# FuseCircuit.net
KiCad netlist of a schematic drawn in Altium Designer
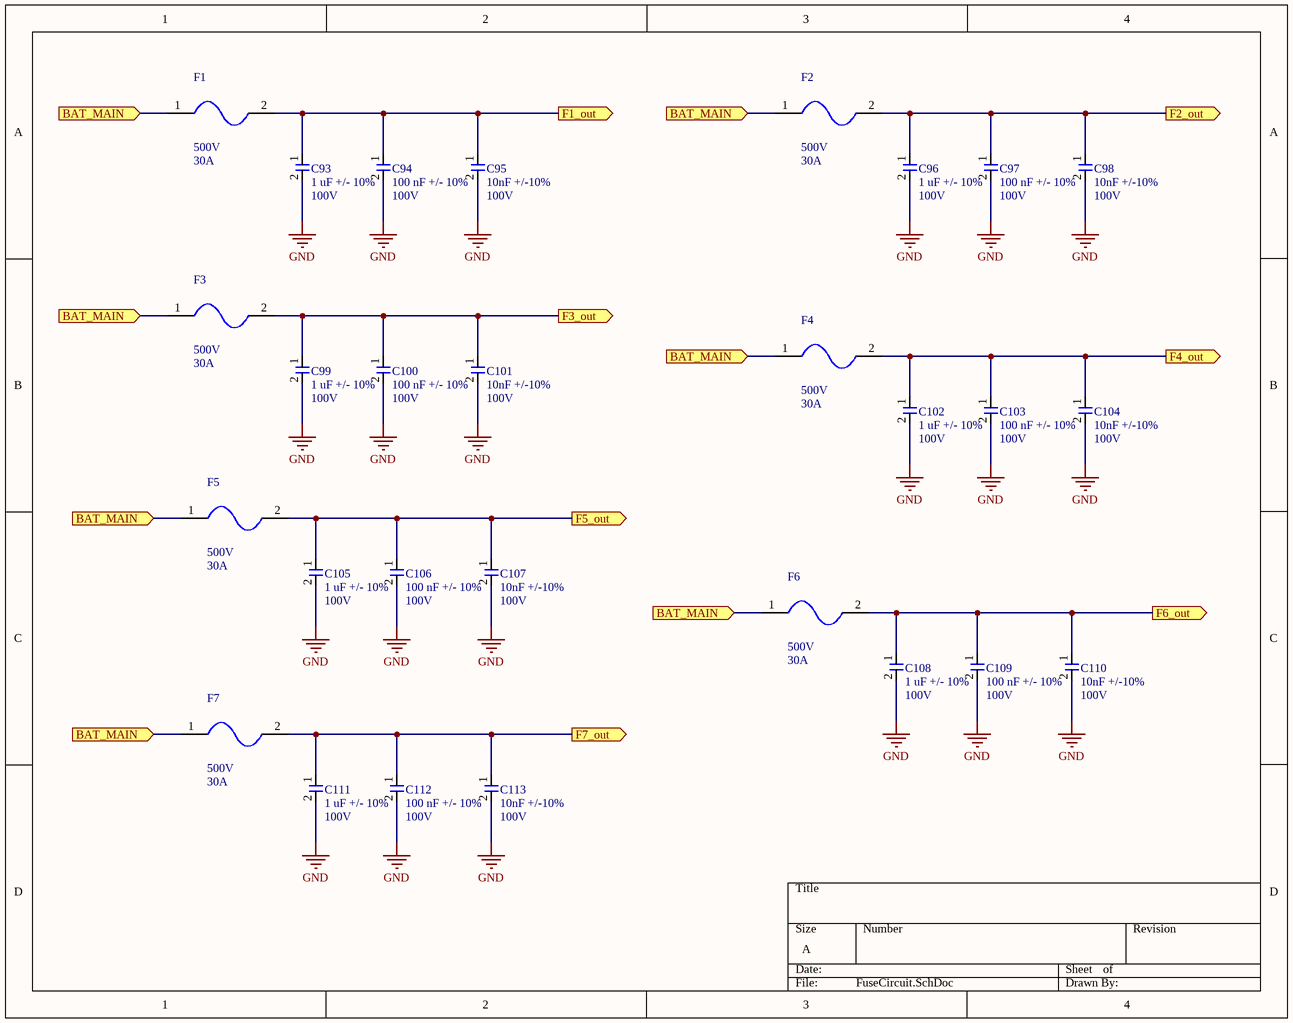
[diagram p0: FuseCircuit.SchDoc]

(export (version "E")
  (design (tool "Eeschema 10.0.6"))
  (components
    (comp (ref "C93")
      (value "C1206X105K101T")
      (footprint "CAP-1206 - duplicate")
      (description "100V 1uF X7R ±10% 1206 Multilayer Ceramic Capacitors MLCC - SMD/SMT ROHS")
      (fields
        (field (name "JLC PART NUMBER") "C106026")
        (field (name "CAPACITANCE") "1 uF +/- 10%")
        (field (name "VOLTAGE") "100V")
      )
      (libsource (lib "MasterLib") (part "CAP-1U-0004-JLC"))
    )
    (comp (ref "C94")
      (value "CC0603KRX7R0BB104")
      (footprint "CAP-0603")
      (description "100V 100nF X7R ±10% 0603 Multilayer Ceramic Capacitors MLCC - SMD/SMT ROHS")
      (fields
        (field (name "JLC PART NUMBER") "C113803")
        (field (name "CAPACITANCE") "100 nF +/- 10%")
        (field (name "VOLTAGE") "100V")
      )
      (libsource (lib "MasterLib") (part "CAP-100N-0002-JLC"))
    )
    (comp (ref "C95")
      (value "CC0603KRX7R0BB103")
      (footprint "CAP-0603")
      (description "100V 10nF X7R ±10% 0603 Multilayer Ceramic Capacitors MLCC - SMD/SMT ROHS")
      (fields
        (field (name "MANUFACTURER") "Yageo")
        (field (name "JLC PART NUMBER") "C107059")
        (field (name "CAPACITANCE") "10nF +/-10%")
        (field (name "VOLTAGE RATING") "100V")
      )
      (libsource (lib "MasterLib") (part "CAP-10N-0003-JLC"))
    )
    (comp (ref "C96")
      (value "C1206X105K101T")
      (footprint "CAP-1206 - duplicate")
      (description "100V 1uF X7R ±10% 1206 Multilayer Ceramic Capacitors MLCC - SMD/SMT ROHS")
      (fields
        (field (name "JLC PART NUMBER") "C106026")
        (field (name "CAPACITANCE") "1 uF +/- 10%")
        (field (name "VOLTAGE") "100V")
      )
      (libsource (lib "MasterLib") (part "CAP-1U-0004-JLC"))
    )
    (comp (ref "C97")
      (value "CC0603KRX7R0BB104")
      (footprint "CAP-0603")
      (description "100V 100nF X7R ±10% 0603 Multilayer Ceramic Capacitors MLCC - SMD/SMT ROHS")
      (fields
        (field (name "JLC PART NUMBER") "C113803")
        (field (name "CAPACITANCE") "100 nF +/- 10%")
        (field (name "VOLTAGE") "100V")
      )
      (libsource (lib "MasterLib") (part "CAP-100N-0002-JLC"))
    )
    (comp (ref "C98")
      (value "CC0603KRX7R0BB103")
      (footprint "CAP-0603")
      (description "100V 10nF X7R ±10% 0603 Multilayer Ceramic Capacitors MLCC - SMD/SMT ROHS")
      (fields
        (field (name "MANUFACTURER") "Yageo")
        (field (name "JLC PART NUMBER") "C107059")
        (field (name "CAPACITANCE") "10nF +/-10%")
        (field (name "VOLTAGE RATING") "100V")
      )
      (libsource (lib "MasterLib") (part "CAP-10N-0003-JLC"))
    )
    (comp (ref "C99")
      (value "C1206X105K101T")
      (footprint "CAP-1206 - duplicate")
      (description "100V 1uF X7R ±10% 1206 Multilayer Ceramic Capacitors MLCC - SMD/SMT ROHS")
      (fields
        (field (name "JLC PART NUMBER") "C106026")
        (field (name "CAPACITANCE") "1 uF +/- 10%")
        (field (name "VOLTAGE") "100V")
      )
      (libsource (lib "MasterLib") (part "CAP-1U-0004-JLC"))
    )
    (comp (ref "C100")
      (value "CC0603KRX7R0BB104")
      (footprint "CAP-0603")
      (description "100V 100nF X7R ±10% 0603 Multilayer Ceramic Capacitors MLCC - SMD/SMT ROHS")
      (fields
        (field (name "JLC PART NUMBER") "C113803")
        (field (name "CAPACITANCE") "100 nF +/- 10%")
        (field (name "VOLTAGE") "100V")
      )
      (libsource (lib "MasterLib") (part "CAP-100N-0002-JLC"))
    )
    (comp (ref "C101")
      (value "CC0603KRX7R0BB103")
      (footprint "CAP-0603")
      (description "100V 10nF X7R ±10% 0603 Multilayer Ceramic Capacitors MLCC - SMD/SMT ROHS")
      (fields
        (field (name "MANUFACTURER") "Yageo")
        (field (name "JLC PART NUMBER") "C107059")
        (field (name "CAPACITANCE") "10nF +/-10%")
        (field (name "VOLTAGE RATING") "100V")
      )
      (libsource (lib "MasterLib") (part "CAP-10N-0003-JLC"))
    )
    (comp (ref "C102")
      (value "C1206X105K101T")
      (footprint "CAP-1206 - duplicate")
      (description "100V 1uF X7R ±10% 1206 Multilayer Ceramic Capacitors MLCC - SMD/SMT ROHS")
      (fields
        (field (name "JLC PART NUMBER") "C106026")
        (field (name "CAPACITANCE") "1 uF +/- 10%")
        (field (name "VOLTAGE") "100V")
      )
      (libsource (lib "MasterLib") (part "CAP-1U-0004-JLC"))
    )
    (comp (ref "C103")
      (value "CC0603KRX7R0BB104")
      (footprint "CAP-0603")
      (description "100V 100nF X7R ±10% 0603 Multilayer Ceramic Capacitors MLCC - SMD/SMT ROHS")
      (fields
        (field (name "JLC PART NUMBER") "C113803")
        (field (name "CAPACITANCE") "100 nF +/- 10%")
        (field (name "VOLTAGE") "100V")
      )
      (libsource (lib "MasterLib") (part "CAP-100N-0002-JLC"))
    )
    (comp (ref "C104")
      (value "CC0603KRX7R0BB103")
      (footprint "CAP-0603")
      (description "100V 10nF X7R ±10% 0603 Multilayer Ceramic Capacitors MLCC - SMD/SMT ROHS")
      (fields
        (field (name "MANUFACTURER") "Yageo")
        (field (name "JLC PART NUMBER") "C107059")
        (field (name "CAPACITANCE") "10nF +/-10%")
        (field (name "VOLTAGE RATING") "100V")
      )
      (libsource (lib "MasterLib") (part "CAP-10N-0003-JLC"))
    )
    (comp (ref "C105")
      (value "C1206X105K101T")
      (footprint "CAP-1206 - duplicate")
      (description "100V 1uF X7R ±10% 1206 Multilayer Ceramic Capacitors MLCC - SMD/SMT ROHS")
      (fields
        (field (name "JLC PART NUMBER") "C106026")
        (field (name "CAPACITANCE") "1 uF +/- 10%")
        (field (name "VOLTAGE") "100V")
      )
      (libsource (lib "MasterLib") (part "CAP-1U-0004-JLC"))
    )
    (comp (ref "C106")
      (value "CC0603KRX7R0BB104")
      (footprint "CAP-0603")
      (description "100V 100nF X7R ±10% 0603 Multilayer Ceramic Capacitors MLCC - SMD/SMT ROHS")
      (fields
        (field (name "JLC PART NUMBER") "C113803")
        (field (name "CAPACITANCE") "100 nF +/- 10%")
        (field (name "VOLTAGE") "100V")
      )
      (libsource (lib "MasterLib") (part "CAP-100N-0002-JLC"))
    )
    (comp (ref "C107")
      (value "CC0603KRX7R0BB103")
      (footprint "CAP-0603")
      (description "100V 10nF X7R ±10% 0603 Multilayer Ceramic Capacitors MLCC - SMD/SMT ROHS")
      (fields
        (field (name "MANUFACTURER") "Yageo")
        (field (name "JLC PART NUMBER") "C107059")
        (field (name "CAPACITANCE") "10nF +/-10%")
        (field (name "VOLTAGE RATING") "100V")
      )
      (libsource (lib "MasterLib") (part "CAP-10N-0003-JLC"))
    )
    (comp (ref "C108")
      (value "C1206X105K101T")
      (footprint "CAP-1206 - duplicate")
      (description "100V 1uF X7R ±10% 1206 Multilayer Ceramic Capacitors MLCC - SMD/SMT ROHS")
      (fields
        (field (name "JLC PART NUMBER") "C106026")
        (field (name "CAPACITANCE") "1 uF +/- 10%")
        (field (name "VOLTAGE") "100V")
      )
      (libsource (lib "MasterLib") (part "CAP-1U-0004-JLC"))
    )
    (comp (ref "C109")
      (value "CC0603KRX7R0BB104")
      (footprint "CAP-0603")
      (description "100V 100nF X7R ±10% 0603 Multilayer Ceramic Capacitors MLCC - SMD/SMT ROHS")
      (fields
        (field (name "JLC PART NUMBER") "C113803")
        (field (name "CAPACITANCE") "100 nF +/- 10%")
        (field (name "VOLTAGE") "100V")
      )
      (libsource (lib "MasterLib") (part "CAP-100N-0002-JLC"))
    )
    (comp (ref "C110")
      (value "CC0603KRX7R0BB103")
      (footprint "CAP-0603")
      (description "100V 10nF X7R ±10% 0603 Multilayer Ceramic Capacitors MLCC - SMD/SMT ROHS")
      (fields
        (field (name "MANUFACTURER") "Yageo")
        (field (name "JLC PART NUMBER") "C107059")
        (field (name "CAPACITANCE") "10nF +/-10%")
        (field (name "VOLTAGE RATING") "100V")
      )
      (libsource (lib "MasterLib") (part "CAP-10N-0003-JLC"))
    )
    (comp (ref "C111")
      (value "C1206X105K101T")
      (footprint "CAP-1206 - duplicate")
      (description "100V 1uF X7R ±10% 1206 Multilayer Ceramic Capacitors MLCC - SMD/SMT ROHS")
      (fields
        (field (name "JLC PART NUMBER") "C106026")
        (field (name "CAPACITANCE") "1 uF +/- 10%")
        (field (name "VOLTAGE") "100V")
      )
      (libsource (lib "MasterLib") (part "CAP-1U-0004-JLC"))
    )
    (comp (ref "C112")
      (value "CC0603KRX7R0BB104")
      (footprint "CAP-0603")
      (description "100V 100nF X7R ±10% 0603 Multilayer Ceramic Capacitors MLCC - SMD/SMT ROHS")
      (fields
        (field (name "JLC PART NUMBER") "C113803")
        (field (name "CAPACITANCE") "100 nF +/- 10%")
        (field (name "VOLTAGE") "100V")
      )
      (libsource (lib "MasterLib") (part "CAP-100N-0002-JLC"))
    )
    (comp (ref "C113")
      (value "CC0603KRX7R0BB103")
      (footprint "CAP-0603")
      (description "100V 10nF X7R ±10% 0603 Multilayer Ceramic Capacitors MLCC - SMD/SMT ROHS")
      (fields
        (field (name "MANUFACTURER") "Yageo")
        (field (name "JLC PART NUMBER") "C107059")
        (field (name "CAPACITANCE") "10nF +/-10%")
        (field (name "VOLTAGE RATING") "100V")
      )
      (libsource (lib "MasterLib") (part "CAP-10N-0003-JLC"))
    )
    (comp (ref "F1")
      (value "3568")
      (footprint "FUSE-ATM-0001")
      (description "Fuse Holder 30 A 500V 1 Circuit Blade Through Hole")
      (fields (field (name "VOLTAGE RATING") "500V") (field (name "CURRENT") "30A"))
      (libsource (lib "MasterLib") (part "FUSE-ATM-0001"))
    )
    (comp (ref "F2")
      (value "3568")
      (footprint "FUSE-ATM-0001")
      (description "Fuse Holder 30 A 500V 1 Circuit Blade Through Hole")
      (fields (field (name "VOLTAGE RATING") "500V") (field (name "CURRENT") "30A"))
      (libsource (lib "MasterLib") (part "FUSE-ATM-0001"))
    )
    (comp (ref "F3")
      (value "3568")
      (footprint "FUSE-ATM-0001")
      (description "Fuse Holder 30 A 500V 1 Circuit Blade Through Hole")
      (fields (field (name "VOLTAGE RATING") "500V") (field (name "CURRENT") "30A"))
      (libsource (lib "MasterLib") (part "FUSE-ATM-0001"))
    )
    (comp (ref "F4")
      (value "3568")
      (footprint "FUSE-ATM-0001")
      (description "Fuse Holder 30 A 500V 1 Circuit Blade Through Hole")
      (fields (field (name "VOLTAGE RATING") "500V") (field (name "CURRENT") "30A"))
      (libsource (lib "MasterLib") (part "FUSE-ATM-0001"))
    )
    (comp (ref "F5")
      (value "3568")
      (footprint "FUSE-ATM-0001")
      (description "Fuse Holder 30 A 500V 1 Circuit Blade Through Hole")
      (fields (field (name "VOLTAGE RATING") "500V") (field (name "CURRENT") "30A"))
      (libsource (lib "MasterLib") (part "FUSE-ATM-0001"))
    )
    (comp (ref "F6")
      (value "3568")
      (footprint "FUSE-ATM-0001")
      (description "Fuse Holder 30 A 500V 1 Circuit Blade Through Hole")
      (fields (field (name "VOLTAGE RATING") "500V") (field (name "CURRENT") "30A"))
      (libsource (lib "MasterLib") (part "FUSE-ATM-0001"))
    )
    (comp (ref "F7")
      (value "3568")
      (footprint "FUSE-ATM-0001")
      (description "Fuse Holder 30 A 500V 1 Circuit Blade Through Hole")
      (fields (field (name "VOLTAGE RATING") "500V") (field (name "CURRENT") "30A"))
      (libsource (lib "MasterLib") (part "FUSE-ATM-0001"))
    )
  )
  (nets
    (net (code "1") (name "/BAT_MAIN") (class "Default")
      (node (ref "F1") (pin "1") (pinfunction "0_1") (pintype "passive"))
      (node (ref "F2") (pin "1") (pinfunction "0_1") (pintype "passive"))
      (node (ref "F3") (pin "1") (pinfunction "0_1") (pintype "passive"))
      (node (ref "F4") (pin "1") (pinfunction "0_1") (pintype "passive"))
      (node (ref "F5") (pin "1") (pinfunction "0_1") (pintype "passive"))
      (node (ref "F6") (pin "1") (pinfunction "0_1") (pintype "passive"))
      (node (ref "F7") (pin "1") (pinfunction "0_1") (pintype "passive"))
    )
    (net (code "2") (name "/F1_out") (class "Default")
      (node (ref "C93") (pin "1") (pinfunction "1_1") (pintype "passive"))
      (node (ref "C94") (pin "1") (pinfunction "1_1") (pintype "passive"))
      (node (ref "C95") (pin "1") (pinfunction "1_1") (pintype "passive"))
      (node (ref "F1") (pin "2") (pinfunction "1_2") (pintype "passive"))
    )
    (net (code "3") (name "/F2_out") (class "Default")
      (node (ref "C96") (pin "1") (pinfunction "1_1") (pintype "passive"))
      (node (ref "C97") (pin "1") (pinfunction "1_1") (pintype "passive"))
      (node (ref "C98") (pin "1") (pinfunction "1_1") (pintype "passive"))
      (node (ref "F2") (pin "2") (pinfunction "1_2") (pintype "passive"))
    )
    (net (code "4") (name "/F3_out") (class "Default")
      (node (ref "C100") (pin "1") (pinfunction "1_1") (pintype "passive"))
      (node (ref "C101") (pin "1") (pinfunction "1_1") (pintype "passive"))
      (node (ref "C99") (pin "1") (pinfunction "1_1") (pintype "passive"))
      (node (ref "F3") (pin "2") (pinfunction "1_2") (pintype "passive"))
    )
    (net (code "5") (name "/F4_out") (class "Default")
      (node (ref "C102") (pin "1") (pinfunction "1_1") (pintype "passive"))
      (node (ref "C103") (pin "1") (pinfunction "1_1") (pintype "passive"))
      (node (ref "C104") (pin "1") (pinfunction "1_1") (pintype "passive"))
      (node (ref "F4") (pin "2") (pinfunction "1_2") (pintype "passive"))
    )
    (net (code "6") (name "/F5_out") (class "Default")
      (node (ref "C105") (pin "1") (pinfunction "1_1") (pintype "passive"))
      (node (ref "C106") (pin "1") (pinfunction "1_1") (pintype "passive"))
      (node (ref "C107") (pin "1") (pinfunction "1_1") (pintype "passive"))
      (node (ref "F5") (pin "2") (pinfunction "1_2") (pintype "passive"))
    )
    (net (code "7") (name "/F6_out") (class "Default")
      (node (ref "C108") (pin "1") (pinfunction "1_1") (pintype "passive"))
      (node (ref "C109") (pin "1") (pinfunction "1_1") (pintype "passive"))
      (node (ref "C110") (pin "1") (pinfunction "1_1") (pintype "passive"))
      (node (ref "F6") (pin "2") (pinfunction "1_2") (pintype "passive"))
    )
    (net (code "8") (name "/F7_out") (class "Default")
      (node (ref "C111") (pin "1") (pinfunction "1_1") (pintype "passive"))
      (node (ref "C112") (pin "1") (pinfunction "1_1") (pintype "passive"))
      (node (ref "C113") (pin "1") (pinfunction "1_1") (pintype "passive"))
      (node (ref "F7") (pin "2") (pinfunction "1_2") (pintype "passive"))
    )
    (net (code "9") (name "GND") (class "Default")
      (node (ref "C100") (pin "2") (pinfunction "2_2") (pintype "passive"))
      (node (ref "C101") (pin "2") (pinfunction "2_2") (pintype "passive"))
      (node (ref "C102") (pin "2") (pinfunction "2_2") (pintype "passive"))
      (node (ref "C103") (pin "2") (pinfunction "2_2") (pintype "passive"))
      (node (ref "C104") (pin "2") (pinfunction "2_2") (pintype "passive"))
      (node (ref "C105") (pin "2") (pinfunction "2_2") (pintype "passive"))
      (node (ref "C106") (pin "2") (pinfunction "2_2") (pintype "passive"))
      (node (ref "C107") (pin "2") (pinfunction "2_2") (pintype "passive"))
      (node (ref "C108") (pin "2") (pinfunction "2_2") (pintype "passive"))
      (node (ref "C109") (pin "2") (pinfunction "2_2") (pintype "passive"))
      (node (ref "C110") (pin "2") (pinfunction "2_2") (pintype "passive"))
      (node (ref "C111") (pin "2") (pinfunction "2_2") (pintype "passive"))
      (node (ref "C112") (pin "2") (pinfunction "2_2") (pintype "passive"))
      (node (ref "C113") (pin "2") (pinfunction "2_2") (pintype "passive"))
      (node (ref "C93") (pin "2") (pinfunction "2_2") (pintype "passive"))
      (node (ref "C94") (pin "2") (pinfunction "2_2") (pintype "passive"))
      (node (ref "C95") (pin "2") (pinfunction "2_2") (pintype "passive"))
      (node (ref "C96") (pin "2") (pinfunction "2_2") (pintype "passive"))
      (node (ref "C97") (pin "2") (pinfunction "2_2") (pintype "passive"))
      (node (ref "C98") (pin "2") (pinfunction "2_2") (pintype "passive"))
      (node (ref "C99") (pin "2") (pinfunction "2_2") (pintype "passive"))
    )
  )
)
